# M627.net
KiCad netlist of a schematic drawn in EAGLE
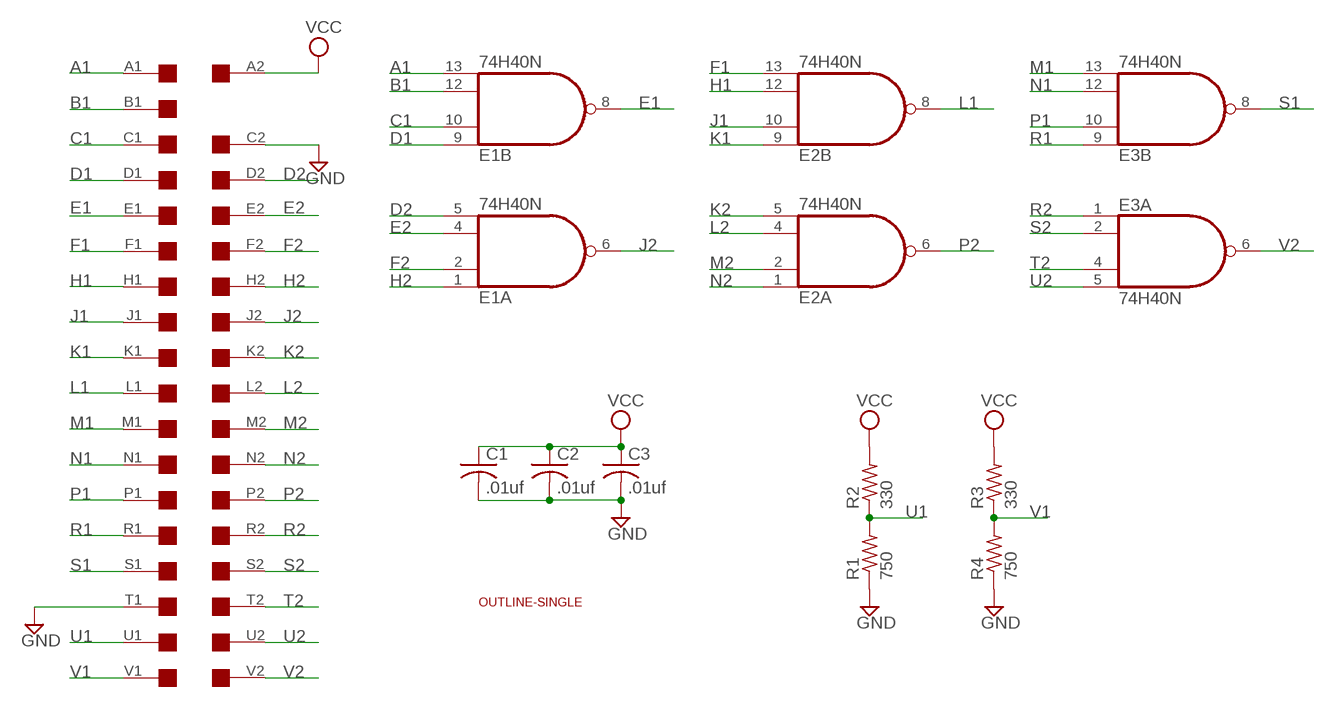
[diagram p0: schematic, sheet 1]

(export (version "E")
  (design (tool "Eeschema 10.0.6"))
  (components
    (comp (ref "C1")
      (value ".01uf")
      (footprint "eagle-import:C050-025X075")
      (libsource (lib "eagle-import") (part "C-US050-025X075"))
    )
    (comp (ref "C2")
      (value ".01uf")
      (footprint "eagle-import:C050-025X075")
      (libsource (lib "eagle-import") (part "C-US050-025X075"))
    )
    (comp (ref "C3")
      (value ".01uf")
      (footprint "eagle-import:C050-025X075")
      (libsource (lib "eagle-import") (part "C-US050-025X075"))
    )
    (comp (ref "E1")
      (value "74H40N")
      (footprint "eagle-import:DIL14")
      (libsource (lib "eagle-import") (part "7420NS"))
    )
    (comp (ref "E2")
      (value "74H40N")
      (footprint "eagle-import:DIL14")
      (libsource (lib "eagle-import") (part "7420NS"))
    )
    (comp (ref "E3")
      (value "74H40N")
      (footprint "eagle-import:DIL14")
      (libsource (lib "eagle-import") (part "7420NS"))
    )
    (comp (ref "R1")
      (value "750")
      (footprint "eagle-import:0207_10")
      (libsource (lib "eagle-import") (part "R-US_0207/10"))
    )
    (comp (ref "R2")
      (value "330")
      (footprint "eagle-import:0207_10")
      (libsource (lib "eagle-import") (part "R-US_0207/10"))
    )
    (comp (ref "R3")
      (value "330")
      (footprint "eagle-import:0207_10")
      (libsource (lib "eagle-import") (part "R-US_0207/10"))
    )
    (comp (ref "R4")
      (value "750")
      (footprint "eagle-import:0207_10")
      (libsource (lib "eagle-import") (part "R-US_0207/10"))
    )
    (comp (ref "U$1")
      (value "OUTLINE-SINGLE")
      (footprint "eagle-import:SINGLE")
      (libsource (lib "eagle-import") (part "OUTLINE-SINGLE"))
    )
    (comp (ref "U$2")
      (value "SINGLE")
      (footprint "eagle-import:EDGE-CON2")
      (libsource (lib "eagle-import") (part "SINGLE"))
    )
  )
  (nets
    (net (code "1") (name "/A1") (class "Default")
      (node (ref "E1") (pin "13") (pinfunction "I3_13") (pintype "input"))
      (node (ref "U$2") (pin "A1") (pinfunction "1_A1") (pintype "bidirectional"))
    )
    (net (code "2") (name "/B1") (class "Default")
      (node (ref "E1") (pin "12") (pinfunction "I2_12") (pintype "input"))
      (node (ref "U$2") (pin "B1") (pinfunction "1_B1") (pintype "bidirectional"))
    )
    (net (code "3") (name "/C1") (class "Default")
      (node (ref "E1") (pin "10") (pinfunction "I1_10") (pintype "input"))
      (node (ref "U$2") (pin "C1") (pinfunction "1_C1") (pintype "bidirectional"))
    )
    (net (code "4") (name "/D1") (class "Default")
      (node (ref "E1") (pin "9") (pinfunction "I0_9") (pintype "input"))
      (node (ref "U$2") (pin "D1") (pinfunction "1_D1") (pintype "bidirectional"))
    )
    (net (code "5") (name "/D2") (class "Default")
      (node (ref "E1") (pin "5") (pinfunction "I3_5") (pintype "input"))
      (node (ref "U$2") (pin "D2") (pinfunction "1_D2") (pintype "bidirectional"))
    )
    (net (code "6") (name "/E1") (class "Default")
      (node (ref "E1") (pin "8") (pinfunction "O_8") (pintype "output"))
      (node (ref "U$2") (pin "E1") (pinfunction "1_E1") (pintype "bidirectional"))
    )
    (net (code "7") (name "/E2") (class "Default")
      (node (ref "E1") (pin "4") (pinfunction "I2_4") (pintype "input"))
      (node (ref "U$2") (pin "E2") (pinfunction "1_E2") (pintype "bidirectional"))
    )
    (net (code "8") (name "/F1") (class "Default")
      (node (ref "E2") (pin "13") (pinfunction "I3_13") (pintype "input"))
      (node (ref "U$2") (pin "F1") (pinfunction "1_F1") (pintype "bidirectional"))
    )
    (net (code "9") (name "/F2") (class "Default")
      (node (ref "E1") (pin "2") (pinfunction "I1_2") (pintype "input"))
      (node (ref "U$2") (pin "F2") (pinfunction "1_F2") (pintype "bidirectional"))
    )
    (net (code "10") (name "/H1") (class "Default")
      (node (ref "E2") (pin "12") (pinfunction "I2_12") (pintype "input"))
      (node (ref "U$2") (pin "H1") (pinfunction "1_H1") (pintype "bidirectional"))
    )
    (net (code "11") (name "/H2") (class "Default")
      (node (ref "E1") (pin "1") (pinfunction "I0_1") (pintype "input"))
      (node (ref "U$2") (pin "H2") (pinfunction "1_H2") (pintype "bidirectional"))
    )
    (net (code "12") (name "/J1") (class "Default")
      (node (ref "E2") (pin "10") (pinfunction "I1_10") (pintype "input"))
      (node (ref "U$2") (pin "J1") (pinfunction "1_J1") (pintype "bidirectional"))
    )
    (net (code "13") (name "/J2") (class "Default")
      (node (ref "E1") (pin "6") (pinfunction "O_6") (pintype "output"))
      (node (ref "U$2") (pin "J2") (pinfunction "1_J2") (pintype "bidirectional"))
    )
    (net (code "14") (name "/K1") (class "Default")
      (node (ref "E2") (pin "9") (pinfunction "I0_9") (pintype "input"))
      (node (ref "U$2") (pin "K1") (pinfunction "1_K1") (pintype "bidirectional"))
    )
    (net (code "15") (name "/K2") (class "Default")
      (node (ref "E2") (pin "5") (pinfunction "I3_5") (pintype "input"))
      (node (ref "U$2") (pin "K2") (pinfunction "1_K2") (pintype "bidirectional"))
    )
    (net (code "16") (name "/L1") (class "Default")
      (node (ref "E2") (pin "8") (pinfunction "O_8") (pintype "output"))
      (node (ref "U$2") (pin "L1") (pinfunction "1_L1") (pintype "bidirectional"))
    )
    (net (code "17") (name "/L2") (class "Default")
      (node (ref "E2") (pin "4") (pinfunction "I2_4") (pintype "input"))
      (node (ref "U$2") (pin "L2") (pinfunction "1_L2") (pintype "bidirectional"))
    )
    (net (code "18") (name "/M1") (class "Default")
      (node (ref "E3") (pin "13") (pinfunction "I3_13") (pintype "input"))
      (node (ref "U$2") (pin "M1") (pinfunction "1_M1") (pintype "bidirectional"))
    )
    (net (code "19") (name "/M2") (class "Default")
      (node (ref "E2") (pin "2") (pinfunction "I1_2") (pintype "input"))
      (node (ref "U$2") (pin "M2") (pinfunction "1_M2") (pintype "bidirectional"))
    )
    (net (code "20") (name "/N1") (class "Default")
      (node (ref "E3") (pin "12") (pinfunction "I2_12") (pintype "input"))
      (node (ref "U$2") (pin "N1") (pinfunction "1_N1") (pintype "bidirectional"))
    )
    (net (code "21") (name "/N2") (class "Default")
      (node (ref "E2") (pin "1") (pinfunction "I0_1") (pintype "input"))
      (node (ref "U$2") (pin "N2") (pinfunction "1_N2") (pintype "bidirectional"))
    )
    (net (code "22") (name "/P1") (class "Default")
      (node (ref "E3") (pin "10") (pinfunction "I1_10") (pintype "input"))
      (node (ref "U$2") (pin "P1") (pinfunction "1_P1") (pintype "bidirectional"))
    )
    (net (code "23") (name "/P2") (class "Default")
      (node (ref "E2") (pin "6") (pinfunction "O_6") (pintype "output"))
      (node (ref "U$2") (pin "P2") (pinfunction "1_P2") (pintype "bidirectional"))
    )
    (net (code "24") (name "/R1") (class "Default")
      (node (ref "E3") (pin "9") (pinfunction "I0_9") (pintype "input"))
      (node (ref "U$2") (pin "R1") (pinfunction "1_R1") (pintype "bidirectional"))
    )
    (net (code "25") (name "/R2") (class "Default")
      (node (ref "E3") (pin "1") (pinfunction "I0_1") (pintype "input"))
      (node (ref "U$2") (pin "R2") (pinfunction "1_R2") (pintype "bidirectional"))
    )
    (net (code "26") (name "/S1") (class "Default")
      (node (ref "E3") (pin "8") (pinfunction "O_8") (pintype "output"))
      (node (ref "U$2") (pin "S1") (pinfunction "1_S1") (pintype "bidirectional"))
    )
    (net (code "27") (name "/S2") (class "Default")
      (node (ref "E3") (pin "2") (pinfunction "I1_2") (pintype "input"))
      (node (ref "U$2") (pin "S2") (pinfunction "1_S2") (pintype "bidirectional"))
    )
    (net (code "28") (name "/T2") (class "Default")
      (node (ref "E3") (pin "4") (pinfunction "I2_4") (pintype "input"))
      (node (ref "U$2") (pin "T2") (pinfunction "1_T2") (pintype "bidirectional"))
    )
    (net (code "29") (name "/U1") (class "Default")
      (node (ref "R1") (pin "2") (pinfunction "2_2") (pintype "passive"))
      (node (ref "R2") (pin "1") (pinfunction "1_1") (pintype "passive"))
      (node (ref "U$2") (pin "U1") (pinfunction "1_U1") (pintype "bidirectional"))
    )
    (net (code "30") (name "/U2") (class "Default")
      (node (ref "E3") (pin "5") (pinfunction "I3_5") (pintype "input"))
      (node (ref "U$2") (pin "U2") (pinfunction "1_U2") (pintype "bidirectional"))
    )
    (net (code "31") (name "/V1") (class "Default")
      (node (ref "R3") (pin "1") (pinfunction "1_1") (pintype "passive"))
      (node (ref "R4") (pin "2") (pinfunction "2_2") (pintype "passive"))
      (node (ref "U$2") (pin "V1") (pinfunction "1_V1") (pintype "bidirectional"))
    )
    (net (code "32") (name "/V2") (class "Default")
      (node (ref "E3") (pin "6") (pinfunction "O_6") (pintype "output"))
      (node (ref "U$2") (pin "V2") (pinfunction "1_V2") (pintype "bidirectional"))
    )
    (net (code "33") (name "GND") (class "Default")
      (node (ref "C1") (pin "2") (pinfunction "2_2") (pintype "passive"))
      (node (ref "C2") (pin "2") (pinfunction "2_2") (pintype "passive"))
      (node (ref "C3") (pin "2") (pinfunction "2_2") (pintype "passive"))
      (node (ref "R1") (pin "1") (pinfunction "1_1") (pintype "passive"))
      (node (ref "R4") (pin "1") (pinfunction "1_1") (pintype "passive"))
      (node (ref "U$2") (pin "C2") (pinfunction "1_C2") (pintype "bidirectional"))
      (node (ref "U$2") (pin "T1") (pinfunction "1_T1") (pintype "bidirectional"))
    )
    (net (code "34") (name "VCC") (class "Default")
      (node (ref "C1") (pin "1") (pinfunction "1_1") (pintype "passive"))
      (node (ref "C2") (pin "1") (pinfunction "1_1") (pintype "passive"))
      (node (ref "C3") (pin "1") (pinfunction "1_1") (pintype "passive"))
      (node (ref "R2") (pin "2") (pinfunction "2_2") (pintype "passive"))
      (node (ref "R3") (pin "2") (pinfunction "2_2") (pintype "passive"))
      (node (ref "U$2") (pin "A2") (pinfunction "1_A2") (pintype "bidirectional"))
    )
  )
)
